# MIDI_TRIGGER_SDSV.net
KiCad netlist of a schematic drawn in EAGLE
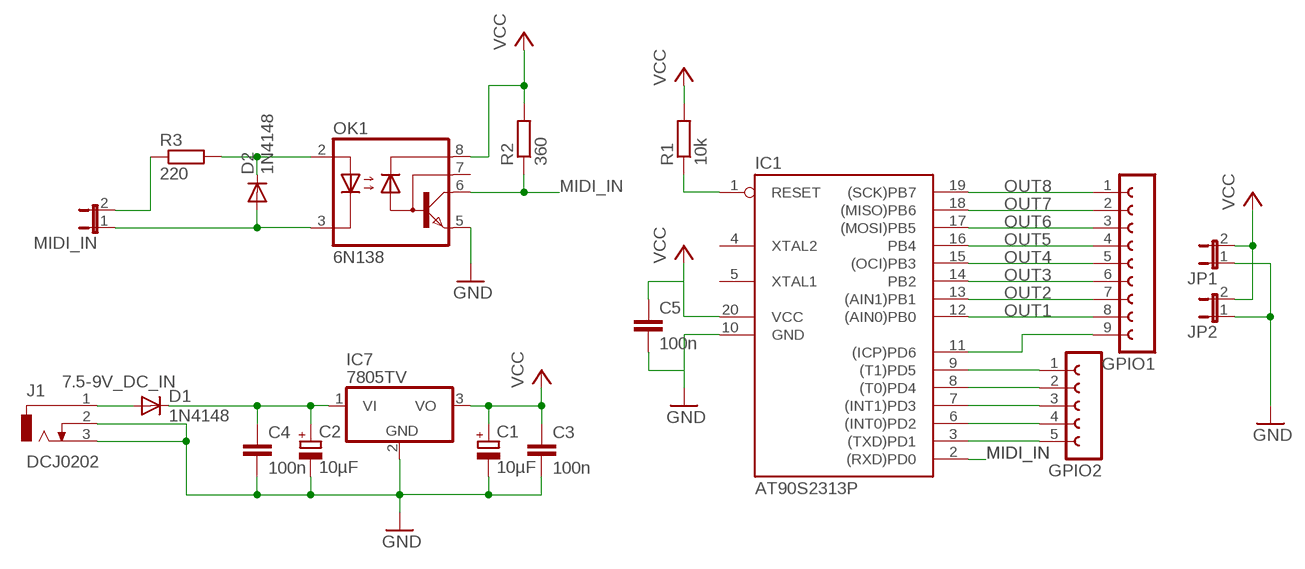
[diagram p0: schematic, sheet 1]

(export (version "E")
  (design (tool "Eeschema 10.0.6"))
  (components
    (comp (ref "C1")
      (value "10µF")
      (footprint "eagle-import:E5-8,5")
      (libsource (lib "eagle-import") (part "CPOL-EUE5-8.5"))
    )
    (comp (ref "C2")
      (value "10µF")
      (footprint "eagle-import:E5-8,5")
      (libsource (lib "eagle-import") (part "CPOL-EUE5-8.5"))
    )
    (comp (ref "C3")
      (value "100n")
      (footprint "eagle-import:C050-025X075")
      (libsource (lib "eagle-import") (part "C-EU050-025X075"))
    )
    (comp (ref "C4")
      (value "100n")
      (footprint "eagle-import:C050-025X075")
      (libsource (lib "eagle-import") (part "C-EU050-025X075"))
    )
    (comp (ref "C5")
      (value "100n")
      (footprint "eagle-import:C050-025X075")
      (libsource (lib "eagle-import") (part "C-EU050-025X075"))
    )
    (comp (ref "D1")
      (value "1N4148")
      (footprint "eagle-import:DO35-7")
      (libsource (lib "eagle-import") (part "1N4148DO35-7"))
    )
    (comp (ref "D2")
      (value "1N4148")
      (footprint "eagle-import:DO35-7")
      (libsource (lib "eagle-import") (part "1N4148DO35-7"))
    )
    (comp (ref "GPIO1")
      (value "FE09-1")
      (footprint "eagle-import:FE09")
      (libsource (lib "eagle-import") (part "FE09-1"))
    )
    (comp (ref "GPIO2")
      (value "FE05-1")
      (footprint "eagle-import:FE05-1")
      (libsource (lib "eagle-import") (part "FE05-1"))
    )
    (comp (ref "IC1")
      (value "AT90S2313P")
      (footprint "eagle-import:DIL20")
      (libsource (lib "eagle-import") (part "AT90S2313P"))
    )
    (comp (ref "IC7")
      (value "7805TV")
      (footprint "eagle-import:TO220V")
      (libsource (lib "eagle-import") (part "78TV05"))
    )
    (comp (ref "J1")
      (value "DCJ0202")
      (footprint "eagle-import:DCJ0202")
      (libsource (lib "eagle-import") (part "DCJ0202"))
    )
    (comp (ref "JP1")
      (value "JP1E")
      (footprint "eagle-import:JP1")
      (libsource (lib "eagle-import") (part "JP1E"))
    )
    (comp (ref "JP2")
      (value "JP1E")
      (footprint "eagle-import:JP1")
      (libsource (lib "eagle-import") (part "JP1E"))
    )
    (comp (ref "MIDI_IN")
      (value "JP1E")
      (footprint "eagle-import:JP1")
      (libsource (lib "eagle-import") (part "JP1E"))
    )
    (comp (ref "OK1")
      (value "6N138")
      (footprint "eagle-import:DIL08")
      (fields (field (name "MF") "FAIRCHILD SEMICONDUCTOR") (field (name "MPN") "6N135"))
      (libsource (lib "eagle-import") (part "6N135"))
    )
    (comp (ref "R1")
      (value "10k")
      (footprint "eagle-import:0204_7")
      (libsource (lib "eagle-import") (part "R-EU_0204/7"))
    )
    (comp (ref "R2")
      (value "360")
      (footprint "eagle-import:0204_7")
      (libsource (lib "eagle-import") (part "R-EU_0204/7"))
    )
    (comp (ref "R3")
      (value "220")
      (footprint "eagle-import:0204_7")
      (libsource (lib "eagle-import") (part "R-EU_0204/7"))
    )
  )
  (nets
    (net (code "1") (name "/7.5-9V_DC_IN") (class "Default")
      (node (ref "D1") (pin "A") (pinfunction "A_A") (pintype "passive"))
      (node (ref "J1") (pin "1") (pinfunction "1_1") (pintype "passive"))
    )
    (net (code "2") (name "/MIDI_IN") (class "Default")
      (node (ref "IC1") (pin "2") (pinfunction "(RXD)PD0_2") (pintype "bidirectional"))
      (node (ref "OK1") (pin "6") (pinfunction "VO_6") (pintype "passive"))
      (node (ref "R2") (pin "1") (pinfunction "1_1") (pintype "passive"))
    )
    (net (code "3") (name "/OUT1") (class "Default")
      (node (ref "GPIO1") (pin "8") (pinfunction "8_8") (pintype "passive"))
      (node (ref "IC1") (pin "12") (pinfunction "(AIN0)PB0_12") (pintype "bidirectional"))
    )
    (net (code "4") (name "/OUT2") (class "Default")
      (node (ref "GPIO1") (pin "7") (pinfunction "7_7") (pintype "passive"))
      (node (ref "IC1") (pin "13") (pinfunction "(AIN1)PB1_13") (pintype "bidirectional"))
    )
    (net (code "5") (name "/OUT3") (class "Default")
      (node (ref "GPIO1") (pin "6") (pinfunction "6_6") (pintype "passive"))
      (node (ref "IC1") (pin "14") (pinfunction "PB2_14") (pintype "bidirectional"))
    )
    (net (code "6") (name "/OUT4") (class "Default")
      (node (ref "GPIO1") (pin "5") (pinfunction "5_5") (pintype "passive"))
      (node (ref "IC1") (pin "15") (pinfunction "(OCI)PB3_15") (pintype "bidirectional"))
    )
    (net (code "7") (name "/OUT5") (class "Default")
      (node (ref "GPIO1") (pin "4") (pinfunction "4_4") (pintype "passive"))
      (node (ref "IC1") (pin "16") (pinfunction "PB4_16") (pintype "bidirectional"))
    )
    (net (code "8") (name "/OUT6") (class "Default")
      (node (ref "GPIO1") (pin "3") (pinfunction "3_3") (pintype "passive"))
      (node (ref "IC1") (pin "17") (pinfunction "(MOSI)PB5_17") (pintype "bidirectional"))
    )
    (net (code "9") (name "/OUT7") (class "Default")
      (node (ref "GPIO1") (pin "2") (pinfunction "2_2") (pintype "passive"))
      (node (ref "IC1") (pin "18") (pinfunction "(MISO)PB6_18") (pintype "bidirectional"))
    )
    (net (code "10") (name "/OUT8") (class "Default")
      (node (ref "GPIO1") (pin "1") (pinfunction "1_1") (pintype "passive"))
      (node (ref "IC1") (pin "19") (pinfunction "(SCK)PB7_19") (pintype "bidirectional"))
    )
    (net (code "11") (name "GND") (class "Default")
      (node (ref "C1") (pin "-") (pinfunction "-_-") (pintype "passive"))
      (node (ref "C2") (pin "-") (pinfunction "-_-") (pintype "passive"))
      (node (ref "C3") (pin "2") (pinfunction "2_2") (pintype "passive"))
      (node (ref "C4") (pin "2") (pinfunction "2_2") (pintype "passive"))
      (node (ref "C5") (pin "2") (pinfunction "2_2") (pintype "passive"))
      (node (ref "IC1") (pin "10") (pinfunction "GND_10") (pintype "power_in"))
      (node (ref "IC7") (pin "2") (pinfunction "GND_2") (pintype "passive"))
      (node (ref "J1") (pin "2") (pinfunction "2_2") (pintype "passive"))
      (node (ref "J1") (pin "3") (pinfunction "3_3") (pintype "passive"))
      (node (ref "JP1") (pin "1") (pinfunction "1_1") (pintype "passive"))
      (node (ref "JP2") (pin "1") (pinfunction "1_1") (pintype "passive"))
      (node (ref "OK1") (pin "5") (pinfunction "GND_5") (pintype "passive"))
    )
    (net (code "12") (name "Net-(IC1-(ICP)PD6)") (class "Default")
      (node (ref "GPIO1") (pin "9") (pinfunction "9_9") (pintype "passive"))
      (node (ref "IC1") (pin "11") (pinfunction "(ICP)PD6_11") (pintype "bidirectional"))
    )
    (net (code "13") (name "Net-(IC1-(INT0)PD2)") (class "Default")
      (node (ref "GPIO2") (pin "4") (pinfunction "4_4") (pintype "passive"))
      (node (ref "IC1") (pin "6") (pinfunction "(INT0)PD2_6") (pintype "bidirectional"))
    )
    (net (code "14") (name "Net-(IC1-(INT1)PD3)") (class "Default")
      (node (ref "GPIO2") (pin "3") (pinfunction "3_3") (pintype "passive"))
      (node (ref "IC1") (pin "7") (pinfunction "(INT1)PD3_7") (pintype "bidirectional"))
    )
    (net (code "15") (name "Net-(IC1-(T0)PD4)") (class "Default")
      (node (ref "GPIO2") (pin "2") (pinfunction "2_2") (pintype "passive"))
      (node (ref "IC1") (pin "8") (pinfunction "(T0)PD4_8") (pintype "bidirectional"))
    )
    (net (code "16") (name "Net-(IC1-(T1)PD5)") (class "Default")
      (node (ref "GPIO2") (pin "1") (pinfunction "1_1") (pintype "passive"))
      (node (ref "IC1") (pin "9") (pinfunction "(T1)PD5_9") (pintype "bidirectional"))
    )
    (net (code "17") (name "Net-(IC1-(TXD)PD1)") (class "Default")
      (node (ref "GPIO2") (pin "5") (pinfunction "5_5") (pintype "passive"))
      (node (ref "IC1") (pin "3") (pinfunction "(TXD)PD1_3") (pintype "bidirectional"))
    )
    (net (code "18") (name "Net-(IC1-RESET)") (class "Default")
      (node (ref "IC1") (pin "1") (pinfunction "RESET_1") (pintype "bidirectional"))
      (node (ref "R1") (pin "1") (pinfunction "1_1") (pintype "passive"))
    )
    (net (code "19") (name "Net-(IC7-VI)") (class "Default")
      (node (ref "C2") (pin "+") (pinfunction "+_+") (pintype "passive"))
      (node (ref "C4") (pin "1") (pinfunction "1_1") (pintype "passive"))
      (node (ref "D1") (pin "C") (pinfunction "C_C") (pintype "passive"))
      (node (ref "IC7") (pin "1") (pinfunction "VI_1") (pintype "input"))
    )
    (net (code "20") (name "Net-(MIDI_IN-Pad2)") (class "Default")
      (node (ref "MIDI_IN") (pin "2") (pinfunction "2_2") (pintype "passive"))
      (node (ref "R3") (pin "1") (pinfunction "1_1") (pintype "passive"))
    )
    (net (code "21") (name "Net-(OK1-A)") (class "Default")
      (node (ref "D2") (pin "C") (pinfunction "C_C") (pintype "passive"))
      (node (ref "OK1") (pin "2") (pinfunction "A_2") (pintype "passive"))
      (node (ref "R3") (pin "2") (pinfunction "2_2") (pintype "passive"))
    )
    (net (code "22") (name "Net-(OK1-C)") (class "Default")
      (node (ref "D2") (pin "A") (pinfunction "A_A") (pintype "passive"))
      (node (ref "MIDI_IN") (pin "1") (pinfunction "1_1") (pintype "passive"))
      (node (ref "OK1") (pin "3") (pinfunction "C_3") (pintype "passive"))
    )
    (net (code "23") (name "VCC") (class "Default")
      (node (ref "C1") (pin "+") (pinfunction "+_+") (pintype "passive"))
      (node (ref "C3") (pin "1") (pinfunction "1_1") (pintype "passive"))
      (node (ref "C5") (pin "1") (pinfunction "1_1") (pintype "passive"))
      (node (ref "IC1") (pin "20") (pinfunction "VCC_20") (pintype "power_in"))
      (node (ref "IC7") (pin "3") (pinfunction "VO_3") (pintype "passive"))
      (node (ref "JP1") (pin "2") (pinfunction "2_2") (pintype "passive"))
      (node (ref "JP2") (pin "2") (pinfunction "2_2") (pintype "passive"))
      (node (ref "OK1") (pin "8") (pinfunction "VCC_8") (pintype "passive"))
      (node (ref "R1") (pin "2") (pinfunction "2_2") (pintype "passive"))
      (node (ref "R2") (pin "2") (pinfunction "2_2") (pintype "passive"))
    )
    (net (code "24") (name "unconnected-(IC1-XTAL1-Pad5)") (class "Default")
      (node (ref "IC1") (pin "5") (pinfunction "XTAL1_5") (pintype "bidirectional"))
    )
    (net (code "25") (name "unconnected-(IC1-XTAL2-Pad4)") (class "Default")
      (node (ref "IC1") (pin "4") (pinfunction "XTAL2_4") (pintype "bidirectional"))
    )
    (net (code "26") (name "unconnected-(OK1-VB-Pad7)") (class "Default")
      (node (ref "OK1") (pin "7") (pinfunction "VB_7") (pintype "passive"))
    )
  )
)
